# labwiz-module_pH.net
KiCad netlist of a schematic drawn in EAGLE
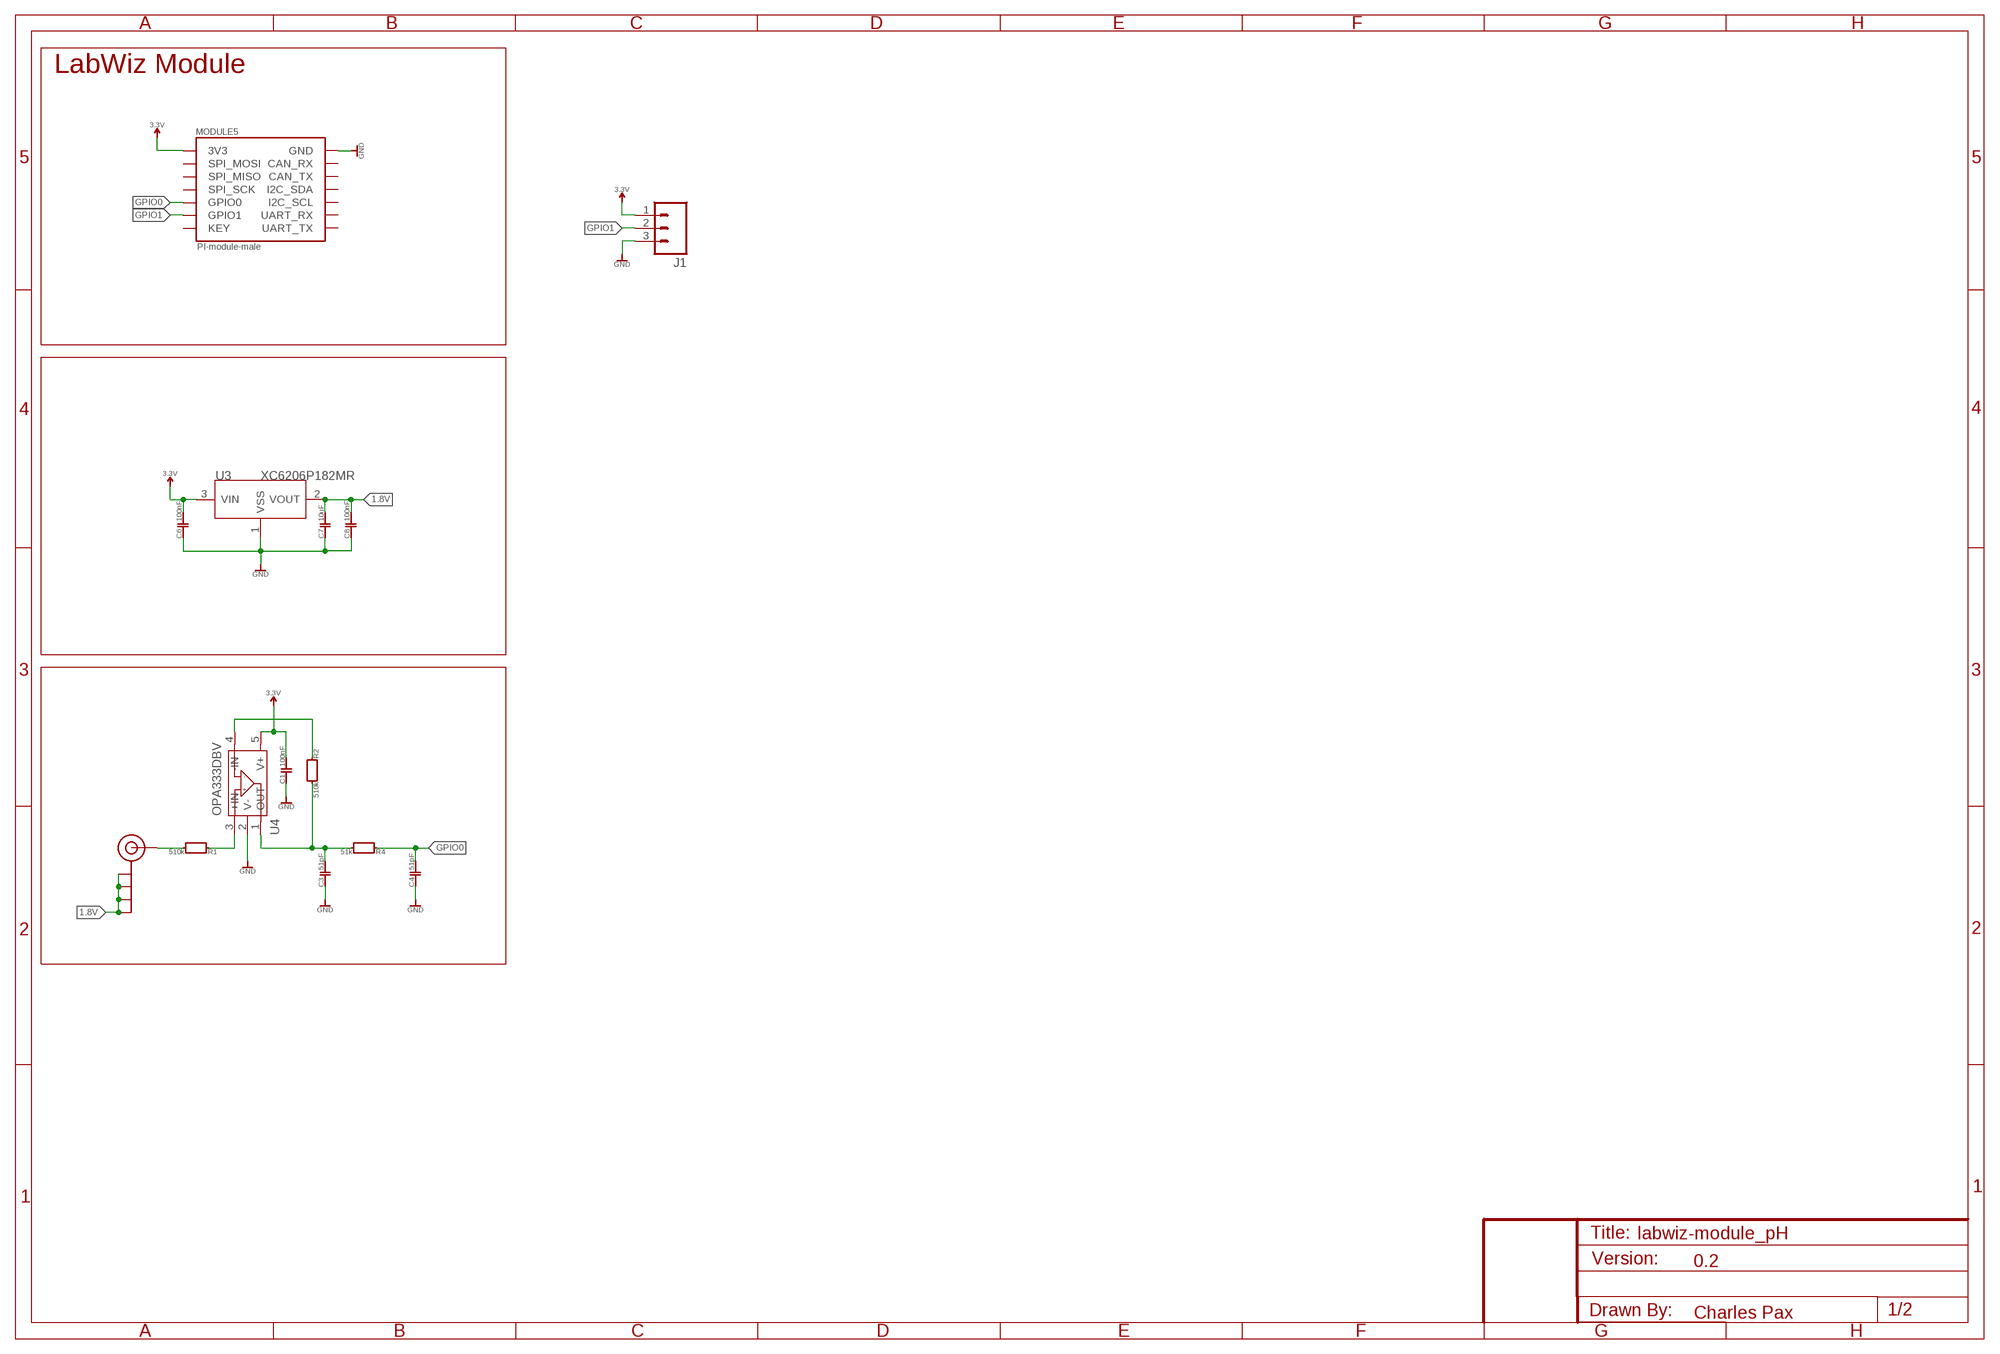
[diagram p0: schematic, sheet 1]

(export (version "E")
  (design (tool "Eeschema 10.0.6"))
  (components
    (comp (ref "C1")
      (value "100nF")
      (footprint "eagle-import:0402")
      (libsource (lib "eagle-import") (part "C0402_100NF"))
    )
    (comp (ref "C3")
      (value "51pF")
      (footprint "eagle-import:0402")
      (libsource (lib "eagle-import") (part "C0402"))
    )
    (comp (ref "C4")
      (value "51pF")
      (footprint "eagle-import:0402")
      (libsource (lib "eagle-import") (part "C0402"))
    )
    (comp (ref "C6")
      (value "100nF")
      (footprint "eagle-import:0402")
      (libsource (lib "eagle-import") (part "C0402_100NF"))
    )
    (comp (ref "C7")
      (value "10uF")
      (footprint "eagle-import:0402")
      (libsource (lib "eagle-import") (part "C0402_10UF"))
    )
    (comp (ref "C8")
      (value "100nF")
      (footprint "eagle-import:0402")
      (libsource (lib "eagle-import") (part "C0402_100NF"))
    )
    (comp (ref "J$1")
      (value "SMA_EDGE")
      (footprint "eagle-import:SMA-EDGE")
      (libsource (lib "eagle-import") (part "SMA_EDGE"))
    )
    (comp (ref "J1")
      (value "M03LOCK_LONGPADS")
      (footprint "eagle-import:1X03_LOCK_LONGPADS")
      (libsource (lib "eagle-import") (part "M03LOCK_LONGPADS"))
    )
    (comp (ref "MODULE5")
      (value "PI-module-male")
      (footprint "eagle-import:M07X2_2MM_EDGE")
      (fields (field (name "MF") "Pax Instruments") (field (name "MPN") "PIxxxx"))
      (libsource (lib "eagle-import") (part "PAX_MODULE_EDGE_MALE_MODULE"))
    )
    (comp (ref "R1")
      (value "510k")
      (footprint "eagle-import:0402")
      (libsource (lib "eagle-import") (part "R0402"))
    )
    (comp (ref "R2")
      (value "510k")
      (footprint "eagle-import:0402")
      (libsource (lib "eagle-import") (part "R0402"))
    )
    (comp (ref "R4")
      (value "51k")
      (footprint "eagle-import:0402")
      (libsource (lib "eagle-import") (part "R0402"))
    )
    (comp (ref "U3")
      (value "XC6206P182MR")
      (footprint "eagle-import:SOT23")
      (libsource (lib "eagle-import") (part "XC6206MR"))
    )
    (comp (ref "U4")
      (value "OPA333DBV")
      (footprint "eagle-import:SOT23-5")
      (libsource (lib "eagle-import") (part "OPA333DBV"))
    )
  )
  (nets
    (net (code "1") (name "1.8V") (class "Default")
      (node (ref "C7") (pin "2") (pinfunction "2_2") (pintype "passive"))
      (node (ref "C8") (pin "2") (pinfunction "2_2") (pintype "passive"))
      (node (ref "J$1") (pin "GND@0") (pinfunction "GND_GND@0") (pintype "bidirectional"))
      (node (ref "J$1") (pin "GND@1") (pinfunction "GND_GND@1") (pintype "bidirectional"))
      (node (ref "J$1") (pin "GND@2") (pinfunction "GND_GND@2") (pintype "bidirectional"))
      (node (ref "J$1") (pin "GND@3") (pinfunction "GND_GND@3") (pintype "bidirectional"))
      (node (ref "U3") (pin "2") (pinfunction "VOUT_2") (pintype "output"))
    )
    (net (code "2") (name "3.3V") (class "Default")
      (node (ref "C1") (pin "2") (pinfunction "2_2") (pintype "passive"))
      (node (ref "C6") (pin "2") (pinfunction "2_2") (pintype "passive"))
      (node (ref "J1") (pin "1") (pinfunction "1_1") (pintype "passive"))
      (node (ref "MODULE5") (pin "P$13") (pinfunction "3V3_P$13") (pintype "power_in"))
      (node (ref "U3") (pin "3") (pinfunction "VIN_3") (pintype "input"))
      (node (ref "U4") (pin "5") (pinfunction "V+_5") (pintype "bidirectional"))
    )
    (net (code "3") (name "GND") (class "Default")
      (node (ref "C1") (pin "1") (pinfunction "1_1") (pintype "passive"))
      (node (ref "C3") (pin "1") (pinfunction "1_1") (pintype "passive"))
      (node (ref "C4") (pin "1") (pinfunction "1_1") (pintype "passive"))
      (node (ref "C6") (pin "1") (pinfunction "1_1") (pintype "passive"))
      (node (ref "C7") (pin "1") (pinfunction "1_1") (pintype "passive"))
      (node (ref "C8") (pin "1") (pinfunction "1_1") (pintype "passive"))
      (node (ref "J1") (pin "3") (pinfunction "3_3") (pintype "passive"))
      (node (ref "MODULE5") (pin "P$14") (pinfunction "GND_P$14") (pintype "power_in"))
      (node (ref "U3") (pin "1") (pinfunction "VSS_1") (pintype "power_in"))
      (node (ref "U4") (pin "2") (pinfunction "V-_2") (pintype "bidirectional"))
    )
    (net (code "4") (name "GPIO0") (class "Default")
      (node (ref "C4") (pin "2") (pinfunction "2_2") (pintype "passive"))
      (node (ref "MODULE5") (pin "P$5") (pinfunction "GPIO0_P$5") (pintype "bidirectional"))
      (node (ref "R4") (pin "2") (pinfunction "2_2") (pintype "passive"))
    )
    (net (code "5") (name "GPIO1") (class "Default")
      (node (ref "J1") (pin "2") (pinfunction "2_2") (pintype "passive"))
      (node (ref "MODULE5") (pin "P$3") (pinfunction "GPIO1_P$3") (pintype "bidirectional"))
    )
    (net (code "6") (name "Net-(J$1-SIGNAL)") (class "Default")
      (node (ref "J$1") (pin "SIG") (pinfunction "SIGNAL_SIG") (pintype "bidirectional"))
      (node (ref "R1") (pin "1") (pinfunction "1_1") (pintype "passive"))
    )
    (net (code "7") (name "Net-(U4-+IN)") (class "Default")
      (node (ref "R1") (pin "2") (pinfunction "2_2") (pintype "passive"))
      (node (ref "U4") (pin "3") (pinfunction "+IN_3") (pintype "bidirectional"))
    )
    (net (code "8") (name "Net-(U4--IN)") (class "Default")
      (node (ref "R2") (pin "2") (pinfunction "2_2") (pintype "passive"))
      (node (ref "U4") (pin "4") (pinfunction "-IN_4") (pintype "bidirectional"))
    )
    (net (code "9") (name "Net-(U4-OUT)") (class "Default")
      (node (ref "C3") (pin "2") (pinfunction "2_2") (pintype "passive"))
      (node (ref "R2") (pin "1") (pinfunction "1_1") (pintype "passive"))
      (node (ref "R4") (pin "1") (pinfunction "1_1") (pintype "passive"))
      (node (ref "U4") (pin "1") (pinfunction "OUT_1") (pintype "bidirectional"))
    )
    (net (code "10") (name "unconnected-(MODULE5-CAN_RX-PadP$12)") (class "Default")
      (node (ref "MODULE5") (pin "P$12") (pinfunction "CAN_RX_P$12") (pintype "bidirectional"))
    )
    (net (code "11") (name "unconnected-(MODULE5-CAN_TX-PadP$10)") (class "Default")
      (node (ref "MODULE5") (pin "P$10") (pinfunction "CAN_TX_P$10") (pintype "bidirectional"))
    )
    (net (code "12") (name "unconnected-(MODULE5-I2C_SCL-PadP$6)") (class "Default")
      (node (ref "MODULE5") (pin "P$6") (pinfunction "I2C_SCL_P$6") (pintype "bidirectional"))
    )
    (net (code "13") (name "unconnected-(MODULE5-I2C_SDA-PadP$8)") (class "Default")
      (node (ref "MODULE5") (pin "P$8") (pinfunction "I2C_SDA_P$8") (pintype "bidirectional"))
    )
    (net (code "14") (name "unconnected-(MODULE5-KEY-PadP$1)") (class "Default")
      (node (ref "MODULE5") (pin "P$1") (pinfunction "KEY_P$1") (pintype "no_connect"))
    )
    (net (code "15") (name "unconnected-(MODULE5-SPI_MISO-PadP$9)") (class "Default")
      (node (ref "MODULE5") (pin "P$9") (pinfunction "SPI_MISO_P$9") (pintype "bidirectional"))
    )
    (net (code "16") (name "unconnected-(MODULE5-SPI_MOSI-PadP$11)") (class "Default")
      (node (ref "MODULE5") (pin "P$11") (pinfunction "SPI_MOSI_P$11") (pintype "bidirectional"))
    )
    (net (code "17") (name "unconnected-(MODULE5-SPI_SCK-PadP$7)") (class "Default")
      (node (ref "MODULE5") (pin "P$7") (pinfunction "SPI_SCK_P$7") (pintype "bidirectional"))
    )
    (net (code "18") (name "unconnected-(MODULE5-UART_RX-PadP$4)") (class "Default")
      (node (ref "MODULE5") (pin "P$4") (pinfunction "UART_RX_P$4") (pintype "bidirectional"))
    )
    (net (code "19") (name "unconnected-(MODULE5-UART_TX-PadP$2)") (class "Default")
      (node (ref "MODULE5") (pin "P$2") (pinfunction "UART_TX_P$2") (pintype "bidirectional"))
    )
  )
)
